# 2_Microcontroller.net
KiCad netlist of a schematic drawn in Altium Designer
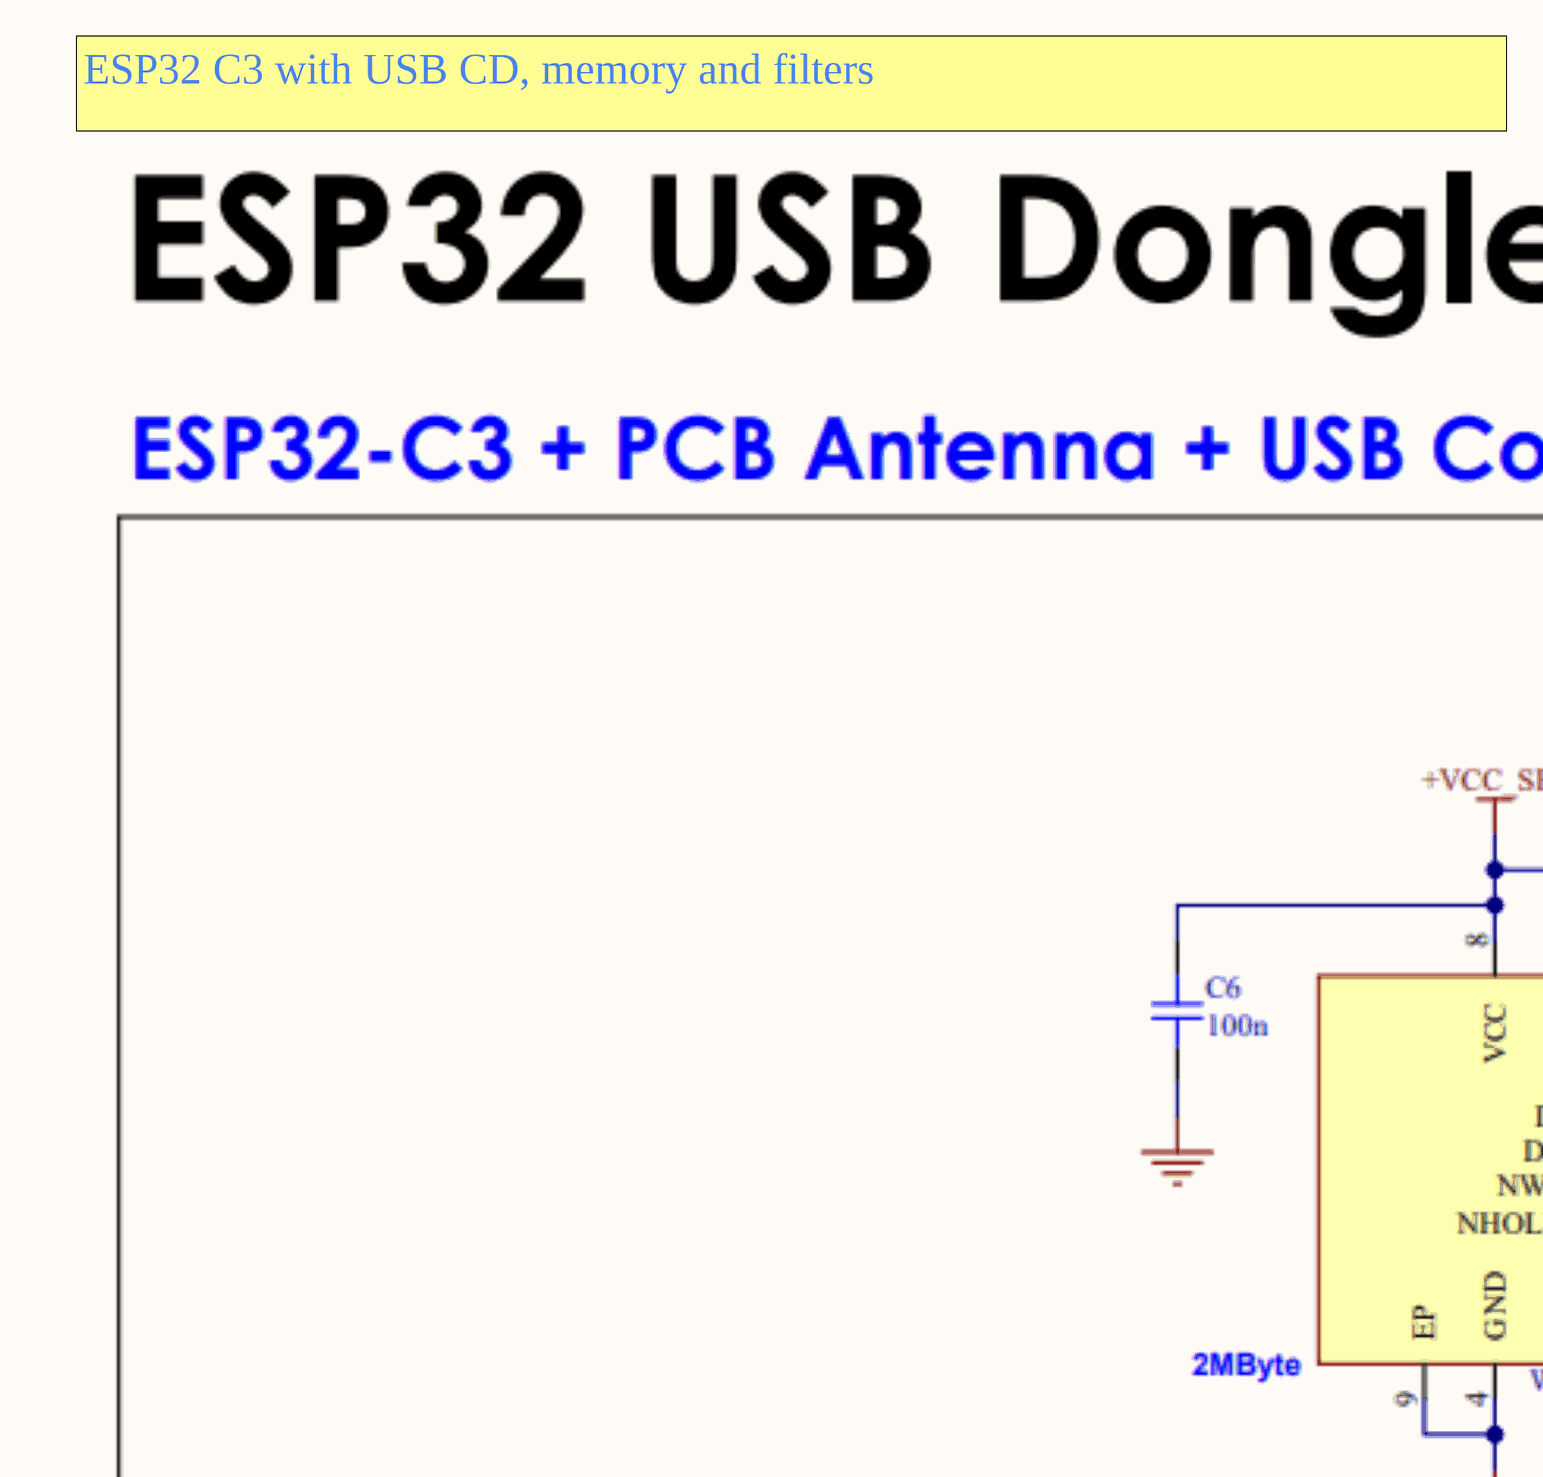
[diagram p0: 2_Microcontroller.SchDoc, top right]
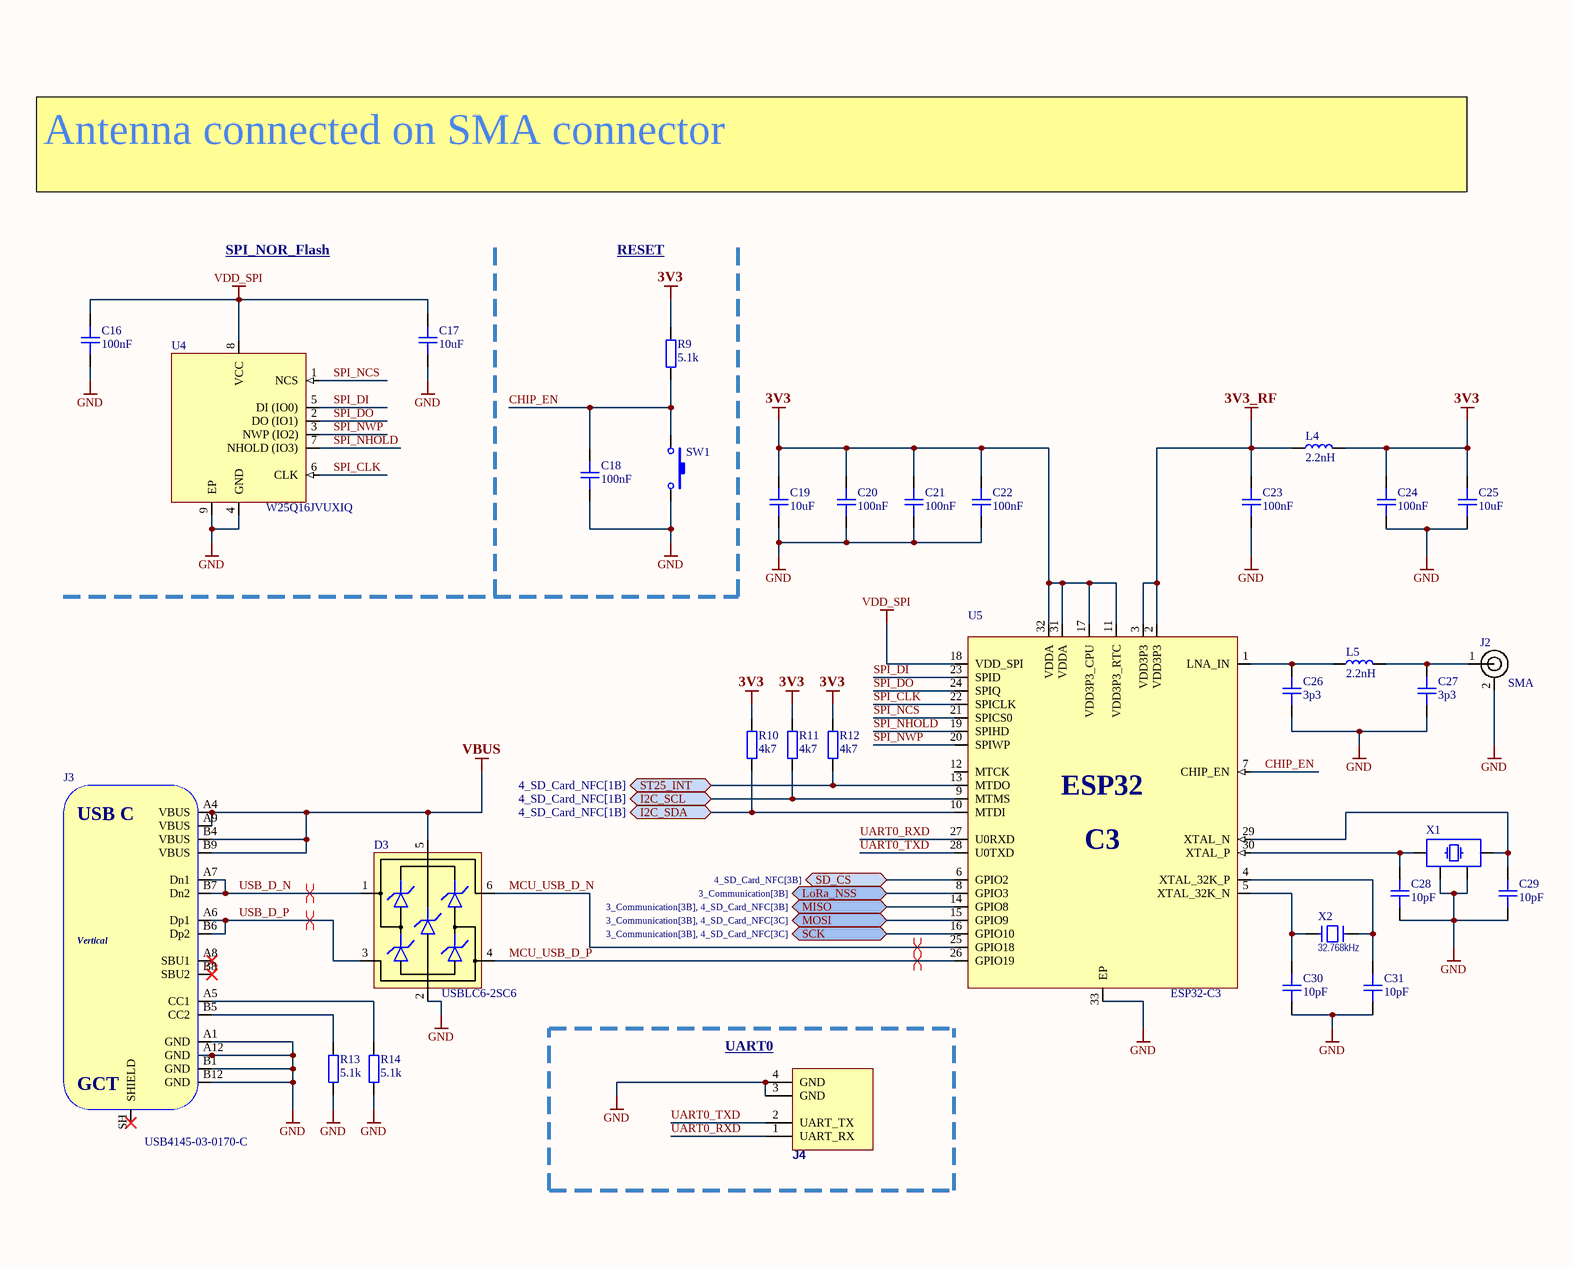
[diagram p1: 2_Microcontroller.SchDoc, bottom left]
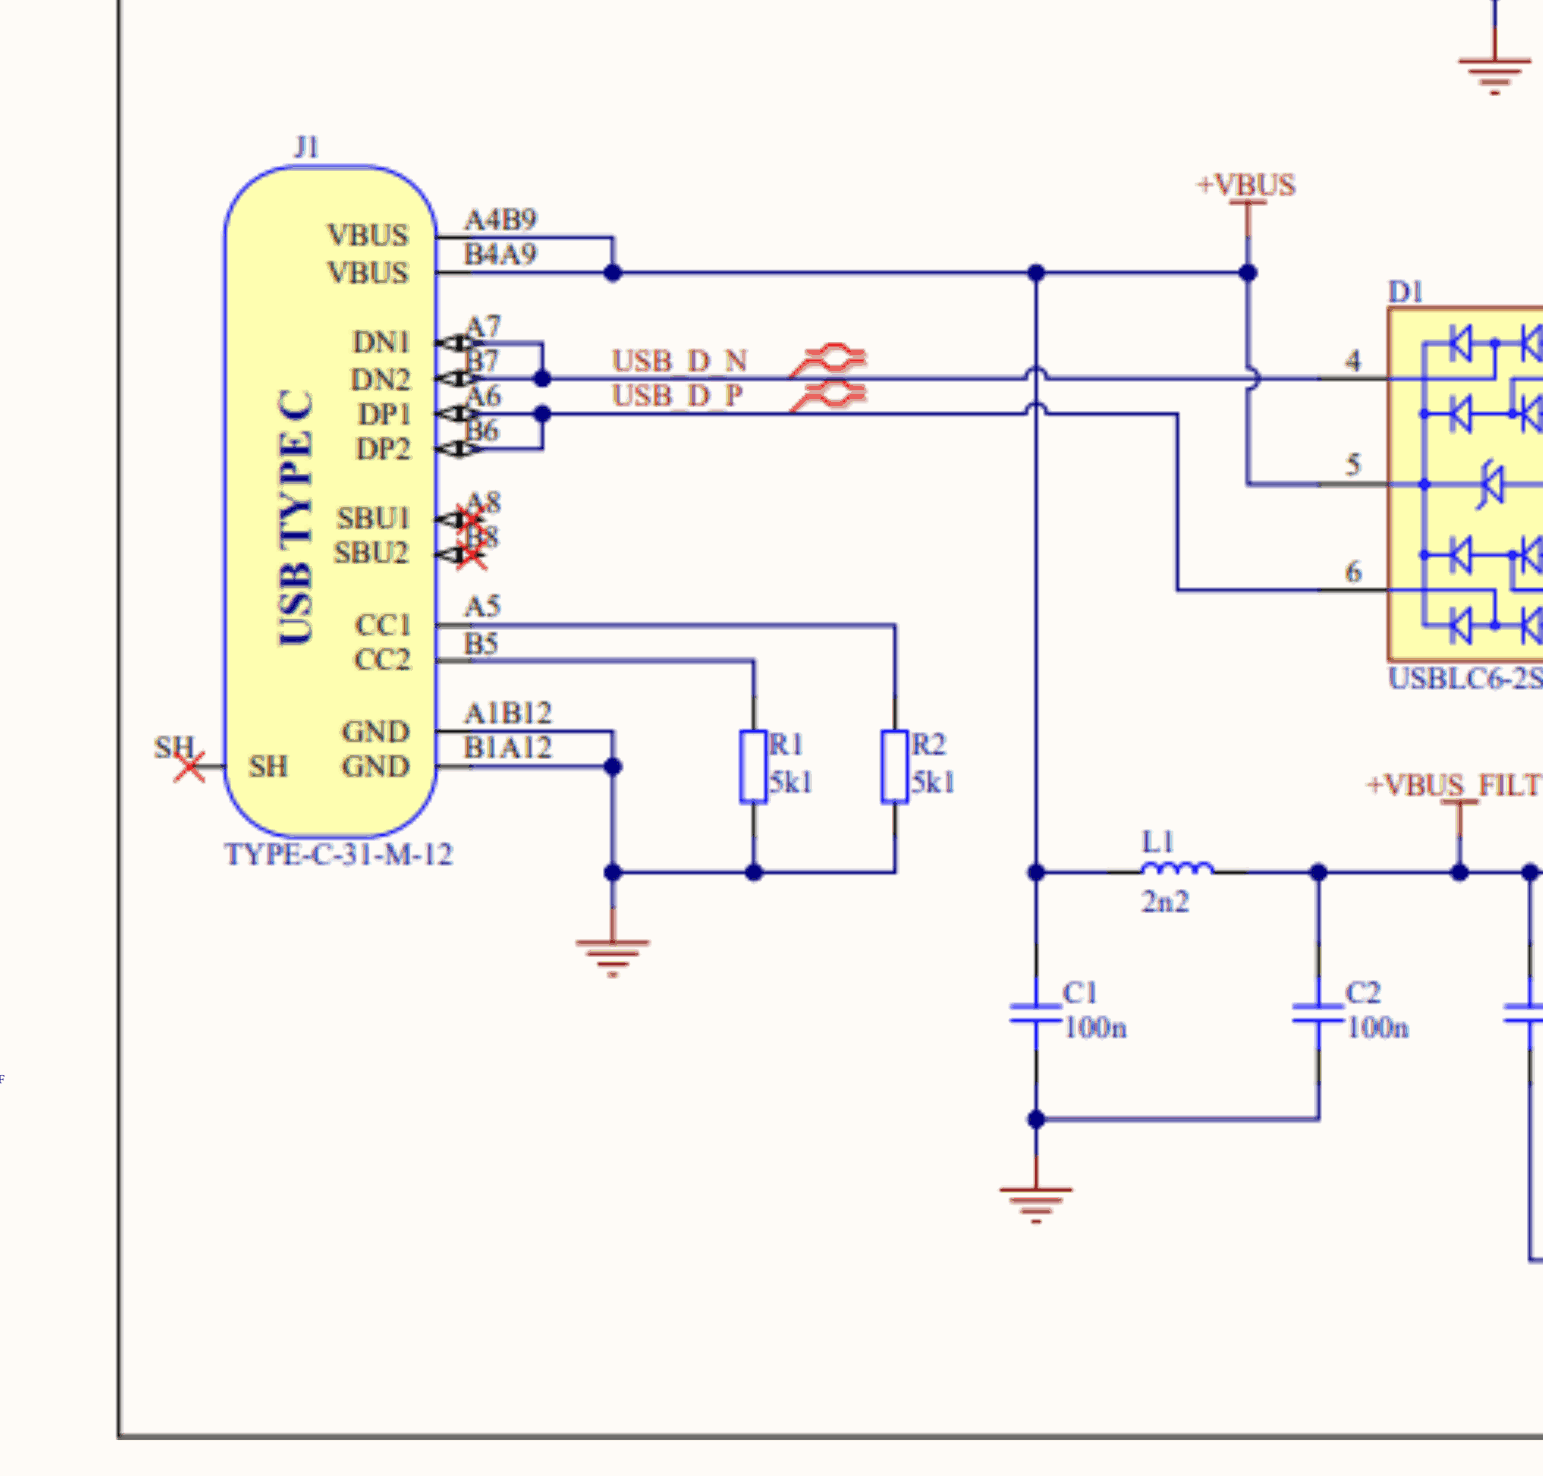
[diagram p2: 2_Microcontroller.SchDoc, bottom right]

(export (version "E")
  (design (tool "Eeschema 10.0.6"))
  (components
    (comp (ref "C16")
      (value "100nF")
      (footprint "CAP_0603")
      (description "Capacitor SMD 0603")
      (libsource (lib "Schlib1") (part "CAP_0603"))
    )
    (comp (ref "C17")
      (value "10uF")
      (footprint "CAP_0805")
      (description "Capacitor SMD 0805")
      (libsource (lib "Schlib1") (part "CAP_0805"))
    )
    (comp (ref "C18")
      (value "100nF")
      (footprint "CAP_0603")
      (description "Capacitor SMD 0603")
      (libsource (lib "Schlib1") (part "CAP_0603"))
    )
    (comp (ref "C19")
      (value "10uF")
      (footprint "CAP_0805")
      (description "Capacitor SMD 0805")
      (libsource (lib "Schlib1") (part "CAP_0805"))
    )
    (comp (ref "C20")
      (value "100nF")
      (footprint "CAP_0603")
      (description "Capacitor SMD 0603")
      (libsource (lib "Schlib1") (part "CAP_0603"))
    )
    (comp (ref "C21")
      (value "100nF")
      (footprint "CAP_0603")
      (description "Capacitor SMD 0603")
      (libsource (lib "Schlib1") (part "CAP_0603"))
    )
    (comp (ref "C22")
      (value "100nF")
      (footprint "CAP_0603")
      (description "Capacitor SMD 0603")
      (libsource (lib "Schlib1") (part "CAP_0603"))
    )
    (comp (ref "C23")
      (value "100nF")
      (footprint "CAP_0603")
      (description "Capacitor SMD 0603")
      (libsource (lib "Schlib1") (part "CAP_0603"))
    )
    (comp (ref "C24")
      (value "100nF")
      (footprint "CAP_0603")
      (description "Capacitor SMD 0603")
      (libsource (lib "Schlib1") (part "CAP_0603"))
    )
    (comp (ref "C25")
      (value "10uF")
      (footprint "CAP_0805")
      (description "Capacitor SMD 0805")
      (libsource (lib "Schlib1") (part "CAP_0805"))
    )
    (comp (ref "C26")
      (value "3p3")
      (footprint "CAP_0603")
      (description "Capacitor SMD 0603")
      (libsource (lib "Schlib1") (part "CAP_0603"))
    )
    (comp (ref "C27")
      (value "3p3")
      (footprint "CAP_0603")
      (description "Capacitor SMD 0603")
      (libsource (lib "Schlib1") (part "CAP_0603"))
    )
    (comp (ref "C28")
      (value "10pF")
      (footprint "CAP_0603")
      (description "Capacitor SMD 0603")
      (libsource (lib "Schlib1") (part "CAP_0603"))
    )
    (comp (ref "C29")
      (value "10pF")
      (footprint "CAP_0603")
      (description "Capacitor SMD 0603")
      (libsource (lib "Schlib1") (part "CAP_0603"))
    )
    (comp (ref "C30")
      (value "10pF")
      (footprint "CAP_0603")
      (description "Capacitor SMD 0603")
      (libsource (lib "Schlib1") (part "CAP_0603"))
    )
    (comp (ref "C31")
      (value "10pF")
      (footprint "CAP_0603")
      (description "Capacitor SMD 0603")
      (libsource (lib "Schlib1") (part "CAP_0603"))
    )
    (comp (ref "D3")
      (value "USBLC6-2SC6")
      (footprint "SOT-23-6")
      (description "Low-Capacitance ESD Protection USB")
      (fields (field (name "MANUFACTURER") "STMicroelectronics"))
      (libsource (lib "Schlib1") (part "USBLC6-2SC6"))
    )
    (comp (ref "J2")
      (value "SMA")
      (footprint "CON-SMA-EDGE-S")
      (description "RF Connector SMA Female 50 Ohms 18 GHz PCB Edge Mount")
      (fields
        (field (name "MANUFACTURER") "RF Solutions")
        (field (name "MANUFACTURER PART NUMBER") "CON-SMA-EDGE-S")
      )
      (libsource (lib "Schlib1") (part "CON-SMA-EDGE-S"))
    )
    (comp (ref "J3")
      (value "USB4145-03-0170-C")
      (footprint "USB4145-03-0170-C")
      (description "USB Connector Type C SMT 16 Pin Vertical")
      (fields (field (name "MANUFACTURER") "GCT"))
      (libsource (lib "Schlib1") (part "USB4145-03-0170-C"))
    )
    (comp (ref "J4") (value "Header1x4") (libsource (lib "Schlib1") (part "Header1x4")))
    (comp (ref "L4")
      (value "2.2nH")
      (footprint "IND_1008")
      (description "Inductor SMD 1008")
      (libsource (lib "Schlib1") (part "IND_1008"))
    )
    (comp (ref "L5")
      (value "2.2nH")
      (footprint "IND_1008")
      (description "Inductor SMD 1008")
      (libsource (lib "Schlib1") (part "IND_1008"))
    )
    (comp (ref "R9")
      (value "5.1k")
      (footprint "RES_0603")
      (description "Resistor SMD 0603")
      (libsource (lib "Schlib1") (part "RES_0603"))
    )
    (comp (ref "R10")
      (value "4k7")
      (footprint "RES_0603")
      (description "Resistor SMD 0603")
      (libsource (lib "Schlib1") (part "RES_0603"))
    )
    (comp (ref "R11")
      (value "4k7")
      (footprint "RES_0603")
      (description "Resistor SMD 0603")
      (libsource (lib "Schlib1") (part "RES_0603"))
    )
    (comp (ref "R12")
      (value "4k7")
      (footprint "RES_0603")
      (description "Resistor SMD 0603")
      (libsource (lib "Schlib1") (part "RES_0603"))
    )
    (comp (ref "R13")
      (value "5.1k")
      (footprint "RES_0603")
      (description "Resistor SMD 0603")
      (libsource (lib "Schlib1") (part "RES_0603"))
    )
    (comp (ref "R14")
      (value "5.1k")
      (footprint "RES_0603")
      (description "Resistor SMD 0603")
      (libsource (lib "Schlib1") (part "RES_0603"))
    )
    (comp (ref "SW1")
      (value "PTS645SM43SMTR92 LFS")
      (footprint "SW_PB")
      (description "Switch")
      (fields (field (name "PUBLISHER") "Altium Limited"))
      (libsource (lib "Schlib1") (part "SW-PB"))
    )
    (comp (ref "U4")
      (value "W25Q16JVUXIQ")
      (footprint "USON-8-2X3MM")
      (description "16M-BIT SERIAL FLASH MEMORY WITH DUAL/QUAD SPI USON-8")
      (fields (field (name "MANUFACTURER") "Winbond"))
      (libsource (lib "Schlib1") (part "W25Q16JVUXIQ"))
    )
    (comp (ref "U5")
      (value "ESP32-C3")
      (footprint "QFN32-5x5")
      (fields (field (name "MANUFACTURER") "Espressif"))
      (libsource (lib "Schlib1") (part "ESP32-C3"))
    )
    (comp (ref "X1")
      (value "XTAL_2016")
      (footprint "XTAL_2016")
      (description "Crystal SMD 4-Pin 2.0x1.6mm")
      (libsource (lib "Schlib1") (part "XTAL_2016"))
    )
    (comp (ref "X2")
      (value "32.768kHz")
      (footprint "SX-3215")
      (description "Crystal")
      (libsource (lib "Schlib1") (part "CRYSTAL_1"))
    )
  )
  (nets
    (net (code "1") (name "/CHIP_EN") (class "Default")
      (node (ref "C18") (pin "2") (pinfunction "2_2") (pintype "passive"))
      (node (ref "R9") (pin "1") (pinfunction "1_1") (pintype "passive"))
      (node (ref "SW1") (pin "1") (pinfunction "1_1") (pintype "passive"))
      (node (ref "U5") (pin "7") (pinfunction "CHIP_EN_7") (pintype "input"))
    )
    (net (code "2") (name "/I2C_SCL") (class "Default")
      (node (ref "R11") (pin "2") (pinfunction "2_2") (pintype "passive"))
      (node (ref "U5") (pin "9") (pinfunction "MTMS_9") (pintype "bidirectional"))
    )
    (net (code "3") (name "/I2C_SDA") (class "Default")
      (node (ref "R10") (pin "2") (pinfunction "2_2") (pintype "passive"))
      (node (ref "U5") (pin "10") (pinfunction "MTDI_10") (pintype "bidirectional"))
    )
    (net (code "4") (name "/LoRa_NSS") (class "Default")
      (node (ref "U5") (pin "8") (pinfunction "GPIO3_8") (pintype "bidirectional"))
    )
    (net (code "5") (name "/MCU_USB_D_N") (class "Default")
      (node (ref "D3") (pin "6") (pinfunction "IO1_6") (pintype "passive"))
      (node (ref "U5") (pin "25") (pinfunction "GPIO18_25") (pintype "passive"))
    )
    (net (code "6") (name "/MCU_USB_D_P") (class "Default")
      (node (ref "D3") (pin "4") (pinfunction "IO2_4") (pintype "passive"))
      (node (ref "U5") (pin "26") (pinfunction "GPIO19_26") (pintype "passive"))
    )
    (net (code "7") (name "/MISO") (class "Default")
      (node (ref "U5") (pin "14") (pinfunction "GPIO8_14") (pintype "bidirectional"))
    )
    (net (code "8") (name "/MOSI") (class "Default")
      (node (ref "U5") (pin "15") (pinfunction "GPIO9_15") (pintype "bidirectional"))
    )
    (net (code "9") (name "/SCK") (class "Default")
      (node (ref "U5") (pin "16") (pinfunction "GPIO10_16") (pintype "bidirectional"))
    )
    (net (code "10") (name "/SD_CS") (class "Default")
      (node (ref "U5") (pin "6") (pinfunction "GPIO2_6") (pintype "bidirectional"))
    )
    (net (code "11") (name "/SPI_CLK") (class "Default")
      (node (ref "U4") (pin "6") (pinfunction "CLK_6") (pintype "input"))
      (node (ref "U5") (pin "22") (pinfunction "SPICLK_22") (pintype "bidirectional"))
    )
    (net (code "12") (name "/SPI_DI") (class "Default")
      (node (ref "U4") (pin "5") (pinfunction "DI_(IO0)_5") (pintype "bidirectional"))
      (node (ref "U5") (pin "23") (pinfunction "SPID_23") (pintype "bidirectional"))
    )
    (net (code "13") (name "/SPI_DO") (class "Default")
      (node (ref "U4") (pin "2") (pinfunction "DO_(IO1)_2") (pintype "bidirectional"))
      (node (ref "U5") (pin "24") (pinfunction "SPIQ_24") (pintype "bidirectional"))
    )
    (net (code "14") (name "/SPI_NCS") (class "Default")
      (node (ref "U4") (pin "1") (pinfunction "NCS_1") (pintype "input"))
      (node (ref "U5") (pin "21") (pinfunction "SPICS0_21") (pintype "bidirectional"))
    )
    (net (code "15") (name "/SPI_NHOLD") (class "Default")
      (node (ref "U4") (pin "7") (pinfunction "NHOLD_(IO3)_7") (pintype "bidirectional"))
      (node (ref "U5") (pin "19") (pinfunction "SPIHD_19") (pintype "bidirectional"))
    )
    (net (code "16") (name "/SPI_NWP") (class "Default")
      (node (ref "U4") (pin "3") (pinfunction "NWP_(IO2)_3") (pintype "bidirectional"))
      (node (ref "U5") (pin "20") (pinfunction "SPIWP_20") (pintype "bidirectional"))
    )
    (net (code "17") (name "/ST25_INT") (class "Default")
      (node (ref "R12") (pin "2") (pinfunction "2_2") (pintype "passive"))
      (node (ref "U5") (pin "13") (pinfunction "MTDO_13") (pintype "bidirectional"))
    )
    (net (code "18") (name "/UART0_RXD") (class "Default")
      (node (ref "J4") (pin "1") (pinfunction "UART_RX_1") (pintype "passive"))
      (node (ref "U5") (pin "27") (pinfunction "U0RXD_27") (pintype "bidirectional"))
    )
    (net (code "19") (name "/UART0_TXD") (class "Default")
      (node (ref "J4") (pin "2") (pinfunction "UART_TX_2") (pintype "passive"))
      (node (ref "U5") (pin "28") (pinfunction "U0TXD_28") (pintype "bidirectional"))
    )
    (net (code "20") (name "/USB_D_N") (class "Default")
      (node (ref "D3") (pin "1") (pinfunction "IO1_1") (pintype "passive"))
      (node (ref "J3") (pin "A7") (pinfunction "Dn1_A7") (pintype "passive"))
      (node (ref "J3") (pin "B7") (pinfunction "Dn2_B7") (pintype "passive"))
    )
    (net (code "21") (name "/USB_D_P") (class "Default")
      (node (ref "D3") (pin "3") (pinfunction "IO2_3") (pintype "passive"))
      (node (ref "J3") (pin "A6") (pinfunction "Dp1_A6") (pintype "passive"))
      (node (ref "J3") (pin "B6") (pinfunction "Dp2_B6") (pintype "passive"))
    )
    (net (code "22") (name "3V3") (class "Default")
      (node (ref "C19") (pin "2") (pinfunction "2_2") (pintype "passive"))
      (node (ref "C20") (pin "2") (pinfunction "2_2") (pintype "passive"))
      (node (ref "C21") (pin "2") (pinfunction "2_2") (pintype "passive"))
      (node (ref "C22") (pin "2") (pinfunction "2_2") (pintype "passive"))
      (node (ref "C24") (pin "2") (pinfunction "2_2") (pintype "passive"))
      (node (ref "C25") (pin "2") (pinfunction "2_2") (pintype "passive"))
      (node (ref "L4") (pin "2") (pinfunction "2_2") (pintype "passive"))
      (node (ref "R10") (pin "1") (pinfunction "1_1") (pintype "passive"))
      (node (ref "R11") (pin "1") (pinfunction "1_1") (pintype "passive"))
      (node (ref "R12") (pin "1") (pinfunction "1_1") (pintype "passive"))
      (node (ref "R9") (pin "2") (pinfunction "2_2") (pintype "passive"))
      (node (ref "U5") (pin "11") (pinfunction "VDD3P3_RTC_11") (pintype "power_in"))
      (node (ref "U5") (pin "17") (pinfunction "VDD3P3_CPU_17") (pintype "power_in"))
      (node (ref "U5") (pin "31") (pinfunction "VDDA_31") (pintype "power_in"))
      (node (ref "U5") (pin "32") (pinfunction "VDDA_32") (pintype "power_in"))
    )
    (net (code "23") (name "3V3_RF") (class "Default")
      (node (ref "C23") (pin "2") (pinfunction "2_2") (pintype "passive"))
      (node (ref "L4") (pin "1") (pinfunction "1_1") (pintype "passive"))
      (node (ref "U5") (pin "2") (pinfunction "VDD3P3_2") (pintype "power_in"))
      (node (ref "U5") (pin "3") (pinfunction "VDD3P3_3") (pintype "power_in"))
    )
    (net (code "24") (name "GND") (class "Default")
      (node (ref "C16") (pin "1") (pinfunction "1_1") (pintype "passive"))
      (node (ref "C17") (pin "1") (pinfunction "1_1") (pintype "passive"))
      (node (ref "C18") (pin "1") (pinfunction "1_1") (pintype "passive"))
      (node (ref "C19") (pin "1") (pinfunction "1_1") (pintype "passive"))
      (node (ref "C20") (pin "1") (pinfunction "1_1") (pintype "passive"))
      (node (ref "C21") (pin "1") (pinfunction "1_1") (pintype "passive"))
      (node (ref "C22") (pin "1") (pinfunction "1_1") (pintype "passive"))
      (node (ref "C23") (pin "1") (pinfunction "1_1") (pintype "passive"))
      (node (ref "C24") (pin "1") (pinfunction "1_1") (pintype "passive"))
      (node (ref "C25") (pin "1") (pinfunction "1_1") (pintype "passive"))
      (node (ref "C26") (pin "1") (pinfunction "1_1") (pintype "passive"))
      (node (ref "C27") (pin "1") (pinfunction "1_1") (pintype "passive"))
      (node (ref "C28") (pin "1") (pinfunction "1_1") (pintype "passive"))
      (node (ref "C29") (pin "1") (pinfunction "1_1") (pintype "passive"))
      (node (ref "C30") (pin "1") (pinfunction "1_1") (pintype "passive"))
      (node (ref "C31") (pin "1") (pinfunction "1_1") (pintype "passive"))
      (node (ref "D3") (pin "2") (pinfunction "GND_2") (pintype "power_in"))
      (node (ref "J2") (pin "2") (pinfunction "2_2") (pintype "passive"))
      (node (ref "J3") (pin "A1") (pinfunction "GND_A1") (pintype "passive"))
      (node (ref "J3") (pin "A12") (pinfunction "GND_A12") (pintype "passive"))
      (node (ref "J3") (pin "B1") (pinfunction "GND_B1") (pintype "passive"))
      (node (ref "J3") (pin "B12") (pinfunction "GND_B12") (pintype "passive"))
      (node (ref "J4") (pin "3") (pinfunction "GND_3") (pintype "passive"))
      (node (ref "J4") (pin "4") (pinfunction "GND_4") (pintype "passive"))
      (node (ref "R13") (pin "1") (pinfunction "1_1") (pintype "passive"))
      (node (ref "R14") (pin "1") (pinfunction "1_1") (pintype "passive"))
      (node (ref "SW1") (pin "2") (pinfunction "2_2") (pintype "passive"))
      (node (ref "U4") (pin "4") (pinfunction "GND_4") (pintype "power_in"))
      (node (ref "U4") (pin "9") (pinfunction "EP_9") (pintype "power_in"))
      (node (ref "U5") (pin "33") (pinfunction "EP_33") (pintype "power_in"))
      (node (ref "X1") (pin "2") (pinfunction "2_2") (pintype "passive"))
      (node (ref "X1") (pin "4") (pinfunction "4_4") (pintype "passive"))
    )
    (net (code "25") (name "Net-(C27-Pad2)") (class "Default")
      (node (ref "C27") (pin "2") (pinfunction "2_2") (pintype "passive"))
      (node (ref "J2") (pin "1") (pinfunction "1_1") (pintype "passive"))
      (node (ref "L5") (pin "2") (pinfunction "2_2") (pintype "passive"))
    )
    (net (code "26") (name "Net-(J3-CC1)") (class "Default")
      (node (ref "J3") (pin "A5") (pinfunction "CC1_A5") (pintype "passive"))
      (node (ref "R14") (pin "2") (pinfunction "2_2") (pintype "passive"))
    )
    (net (code "27") (name "Net-(J3-CC2)") (class "Default")
      (node (ref "J3") (pin "B5") (pinfunction "CC2_B5") (pintype "passive"))
      (node (ref "R13") (pin "2") (pinfunction "2_2") (pintype "passive"))
    )
    (net (code "28") (name "Net-(U5-LNA_IN)") (class "Default")
      (node (ref "C26") (pin "2") (pinfunction "2_2") (pintype "passive"))
      (node (ref "L5") (pin "1") (pinfunction "1_1") (pintype "passive"))
      (node (ref "U5") (pin "1") (pinfunction "LNA_IN_1") (pintype "bidirectional"))
    )
    (net (code "29") (name "Net-(U5-XTAL_32K_N)") (class "Default")
      (node (ref "C30") (pin "2") (pinfunction "2_2") (pintype "passive"))
      (node (ref "U5") (pin "5") (pinfunction "XTAL_32K_N_5") (pintype "bidirectional"))
      (node (ref "X2") (pin "2") (pinfunction "2_2") (pintype "passive"))
    )
    (net (code "30") (name "Net-(U5-XTAL_32K_P)") (class "Default")
      (node (ref "C31") (pin "2") (pinfunction "2_2") (pintype "passive"))
      (node (ref "U5") (pin "4") (pinfunction "XTAL_32K_P_4") (pintype "bidirectional"))
      (node (ref "X2") (pin "1") (pinfunction "1_1") (pintype "passive"))
    )
    (net (code "31") (name "Net-(U5-XTAL_N)") (class "Default")
      (node (ref "C29") (pin "2") (pinfunction "2_2") (pintype "passive"))
      (node (ref "U5") (pin "29") (pinfunction "XTAL_N_29") (pintype "input"))
      (node (ref "X1") (pin "3") (pinfunction "3_3") (pintype "passive"))
    )
    (net (code "32") (name "Net-(U5-XTAL_P)") (class "Default")
      (node (ref "C28") (pin "2") (pinfunction "2_2") (pintype "passive"))
      (node (ref "U5") (pin "30") (pinfunction "XTAL_P_30") (pintype "input"))
      (node (ref "X1") (pin "1") (pinfunction "1_1") (pintype "passive"))
    )
    (net (code "33") (name "VBUS") (class "Default")
      (node (ref "D3") (pin "5") (pinfunction "VBUS_5") (pintype "power_in"))
      (node (ref "J3") (pin "A4") (pinfunction "VBUS_A4") (pintype "passive"))
      (node (ref "J3") (pin "A9") (pinfunction "VBUS_A9") (pintype "passive"))
      (node (ref "J3") (pin "B4") (pinfunction "VBUS_B4") (pintype "passive"))
      (node (ref "J3") (pin "B9") (pinfunction "VBUS_B9") (pintype "passive"))
    )
    (net (code "34") (name "VDD_SPI") (class "Default")
      (node (ref "C16") (pin "2") (pinfunction "2_2") (pintype "passive"))
      (node (ref "C17") (pin "2") (pinfunction "2_2") (pintype "passive"))
      (node (ref "U4") (pin "8") (pinfunction "VCC_8") (pintype "power_in"))
      (node (ref "U5") (pin "18") (pinfunction "VDD_SPI_18") (pintype "power_in"))
    )
    (net (code "35") (name "unconnected-(J3-SBU1-PadA8)") (class "Default")
      (node (ref "J3") (pin "A8") (pinfunction "SBU1_A8") (pintype "passive+no_connect"))
    )
    (net (code "36") (name "unconnected-(J3-SBU2-PadB8)") (class "Default")
      (node (ref "J3") (pin "B8") (pinfunction "SBU2_B8") (pintype "passive+no_connect"))
    )
    (net (code "37") (name "unconnected-(J3-SHIELD-PadSH)") (class "Default")
      (node (ref "J3") (pin "SH") (pinfunction "SHIELD_SH") (pintype "passive+no_connect"))
    )
    (net (code "38") (name "unconnected-(U5-MTCK-Pad12)") (class "Default")
      (node (ref "U5") (pin "12") (pinfunction "MTCK_12") (pintype "bidirectional"))
    )
  )
)
